# 02_-_Power_Supplies.net
KiCad netlist of a schematic drawn in Altium Designer
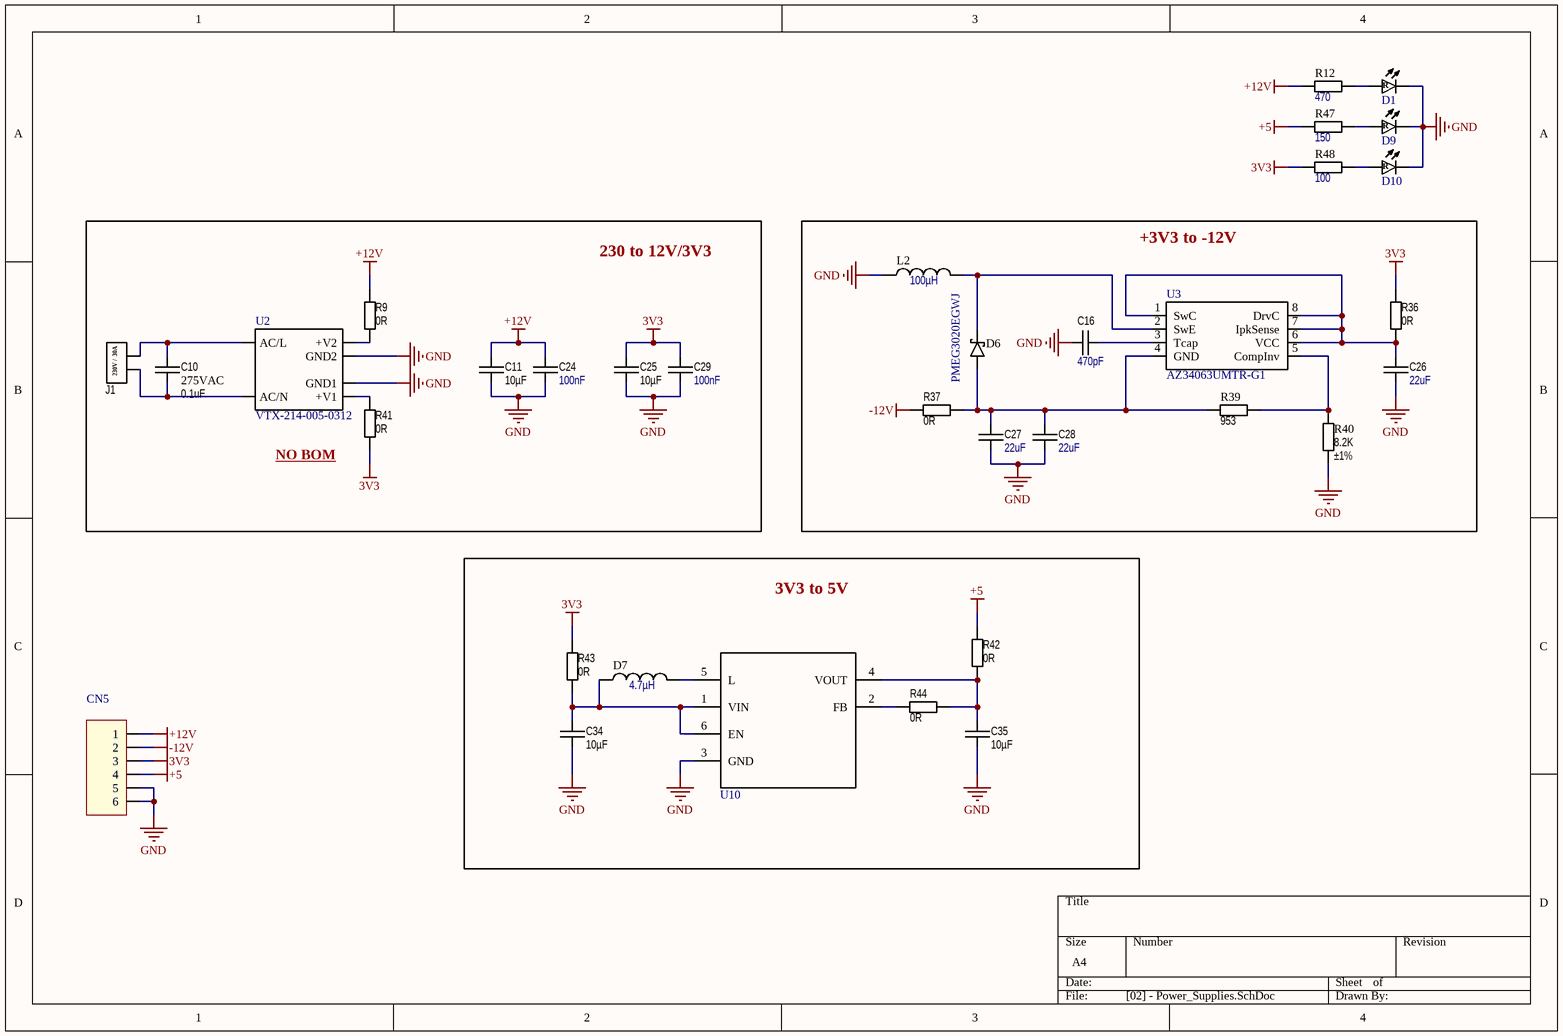
[diagram p0: [02] - Power_Supplies.SchDoc]

(export (version "E")
  (design (tool "Eeschema 10.0.6"))
  (components
    (comp (ref "C10")
      (value "0.1uF")
      (footprint "ECQL")
      (description "0.1µF Film Capacitor 275V  Polyester, Metallized Radial")
      (fields
        (field (name "PARTNUMBER") "ECQ-U2A104ML")
        (field (name "MANUFACTURER") "Panasonic Electronic Components")
        (field (name "VOLTAGE") "275VAC")
      )
      (libsource (lib "myLibrary") (part "CAPC_0.1uF_RADIAL_275VAC"))
    )
    (comp (ref "C11")
      (value "10µF")
      (footprint "CAP 0603/1608")
      (description "10µF ±20% 25V Ceramic Capacitor X5R 0603 (1608 Metric)")
      (fields
        (field (name "PARTNUMBER") "GRM188R61E106MA73D")
        (field (name "MANUFACTURER") "Murata Electronics")
      )
      (libsource (lib "myLibrary") (part "CAPC_10uF_0603_25V"))
    )
    (comp (ref "C16")
      (value "470pF")
      (footprint "CAP 0603/1608")
      (description "470pF ±10% 50V Ceramic Capacitor X7R 0603 (1608 Metric)")
      (fields (field (name "PARTNUMBER") "CC0603KRX7R9BB471") (field (name "MANUFACTURER") "Yageo"))
      (libsource (lib "myLibrary") (part "CAPC_470pF_0603_50V"))
    )
    (comp (ref "C24")
      (value "100nF")
      (footprint "CAP 0603/1608")
      (description "1µF ±10% 16V Ceramic Capacitor X5R 0603 (1608 Metric)")
      (fields (field (name "PARTNUMBER") "CC0603KRX5R7BB105") (field (name "MANUFACTURER") "Yageo"))
      (libsource (lib "myLibrary") (part "CAPC_100NF_0603_50V"))
    )
    (comp (ref "C25")
      (value "10µF")
      (footprint "CAP 0603/1608")
      (description "10µF ±20% 25V Ceramic Capacitor X5R 0603 (1608 Metric)")
      (fields
        (field (name "PARTNUMBER") "GRM188R61E106MA73D")
        (field (name "MANUFACTURER") "Murata Electronics")
      )
      (libsource (lib "myLibrary") (part "CAPC_10uF_0603_25V"))
    )
    (comp (ref "C26")
      (value "22uF")
      (footprint "CAP 0603/1608")
      (description "22µF ±20% 6.3V Ceramic Capacitor X5R 0603 (1608 Metric)")
      (fields
        (field (name "PARTNUMBER") "GRM188R60J226MEA0D")
        (field (name "MANUFACTURER") "Murata Electronics")
      )
      (libsource (lib "myLibrary") (part "CAPC_22uF_0603_6.3V"))
    )
    (comp (ref "C27")
      (value "22uF")
      (footprint "CAP 0603/1608")
      (description "22µF ±20% 6.3V Ceramic Capacitor X5R 0603 (1608 Metric)")
      (fields
        (field (name "PARTNUMBER") "GRM188R60J226MEA0D")
        (field (name "MANUFACTURER") "Murata Electronics")
      )
      (libsource (lib "myLibrary") (part "CAPC_22uF_0603_6.3V"))
    )
    (comp (ref "C28")
      (value "22uF")
      (footprint "CAP 0603/1608")
      (description "22µF ±20% 6.3V Ceramic Capacitor X5R 0603 (1608 Metric)")
      (fields
        (field (name "PARTNUMBER") "GRM188R60J226MEA0D")
        (field (name "MANUFACTURER") "Murata Electronics")
      )
      (libsource (lib "myLibrary") (part "CAPC_22uF_0603_6.3V"))
    )
    (comp (ref "C29")
      (value "100nF")
      (footprint "CAP 0603/1608")
      (description "1µF ±10% 16V Ceramic Capacitor X5R 0603 (1608 Metric)")
      (fields (field (name "PARTNUMBER") "CC0603KRX5R7BB105") (field (name "MANUFACTURER") "Yageo"))
      (libsource (lib "myLibrary") (part "CAPC_100NF_0603_50V"))
    )
    (comp (ref "C34")
      (value "10µF")
      (footprint "CAP 0603/1608")
      (description "10µF ±20% 25V Ceramic Capacitor X5R 0603 (1608 Metric)")
      (fields
        (field (name "PARTNUMBER") "GRM188R61E106MA73D")
        (field (name "MANUFACTURER") "Murata Electronics")
      )
      (libsource (lib "myLibrary") (part "CAPC_10uF_0603_25V"))
    )
    (comp (ref "C35")
      (value "10µF")
      (footprint "CAP 0603/1608")
      (description "10µF ±20% 25V Ceramic Capacitor X5R 0603 (1608 Metric)")
      (fields
        (field (name "PARTNUMBER") "GRM188R61E106MA73D")
        (field (name "MANUFACTURER") "Murata Electronics")
      )
      (libsource (lib "myLibrary") (part "CAPC_10uF_0603_25V"))
    )
    (comp (ref "CN5")
      (value "61300411121")
      (footprint "Terminal_6")
      (description "Connector Header Through Hole 4 position 0.100\" (2.54mm)")
      (fields (field (name "MANUFACTURER") "Wurth Electronics Inc."))
      (libsource (lib "myLibrary") (part "CONN_6POS"))
    )
    (comp (ref "D1")
      (value "SML-D12U1WT86")
      (footprint "LED-0603")
      (description "Red 620nm LED Indication - Discrete 2.2V 0603 (1608 Metric)")
      (fields (field (name "MANUFACTURER") "Rohm Semiconductor"))
      (libsource (lib "myLibrary") (part "LED_RED"))
    )
    (comp (ref "D6")
      (value "PMEG3020EGWJ")
      (footprint "SOD123")
      (description "Diode Schottky 30V 2A Surface Mount SOD-123")
      (fields (field (name "MANUFACTURER") "Nexperia USA Inc."))
      (libsource (lib "myLibrary") (part "DIODE_PMEG"))
    )
    (comp (ref "D7")
      (value "4.7µH")
      (footprint "IND_LQH2HPN4R7MJRL")
      (description "4.7µH Shielded Wirewound Inductor 770mA 204mOhm Max 1008 (2520 Metric)")
      (fields (field (name "PARTNUMBER") "LQH2HPN4R7MJRL") (field (name "MANUFACTURER") "Murata Electronics"))
      (libsource (lib "myLibrary") (part "IND_4.7uH_170mOhm _Murata"))
    )
    (comp (ref "D9")
      (value "SML-D12U1WT86")
      (footprint "LED-0603")
      (description "Red 620nm LED Indication - Discrete 2.2V 0603 (1608 Metric)")
      (fields (field (name "MANUFACTURER") "Rohm Semiconductor"))
      (libsource (lib "myLibrary") (part "LED_RED"))
    )
    (comp (ref "D10")
      (value "SML-D12U1WT86")
      (footprint "LED-0603")
      (description "Red 620nm LED Indication - Discrete 2.2V 0603 (1608 Metric)")
      (fields (field (name "MANUFACTURER") "Rohm Semiconductor"))
      (libsource (lib "myLibrary") (part "LED_RED"))
    )
    (comp (ref "J1")
      (value "1868076")
      (footprint "30Amp_Connector")
      (description "2 Position Wire to Board Terminal Block Horizontal with Board 0.300\" (7.62mm) Through Hole")
      (fields (field (name "MANUFACTURER") "Phoenix Contact"))
      (libsource (lib "myLibrary") (part "TERM_BLK_02_30A"))
    )
    (comp (ref "L2")
      (value "100µH")
      (footprint "IND_1210")
      (description "100µH Unshielded Wirewound Inductor 150mA 1.4Ohm 1210 (3225 Metric)")
      (fields (field (name "PARTNUMBER") "LBC3225T101KR") (field (name "MANUFACTURER") "Taiyo Yuden"))
      (libsource (lib "myLibrary") (part "IND_100uH"))
    )
    (comp (ref "R9")
      (value "0R")
      (footprint "R0603")
      (description "RES 0R 0603 JUMPER")
      (fields (field (name "PARTNUMBER") "RC0603JR-070RL") (field (name "MANUFACTURER") "Yageo"))
      (libsource (lib "myLibrary") (part "RES_0R_0603_JUMPER"))
    )
    (comp (ref "R12")
      (value "470")
      (footprint "R0603")
      (description "470 Ohms ±1% 0.1W, 1/10W Chip Resistor 0603 (1608 Metric) Moisture Resistant Thick Film")
      (fields (field (name "PARTNUMBER") "RC0603FR-07470RL") (field (name "MANUFACTURER") "Yageo"))
      (libsource (lib "myLibrary") (part "RES_470_0603_1%_1"))
    )
    (comp (ref "R36")
      (value "0R")
      (footprint "R0603")
      (description "RES 0R 0603 JUMPER")
      (fields (field (name "PARTNUMBER") "RC0603JR-070RL") (field (name "MANUFACTURER") "Yageo"))
      (libsource (lib "myLibrary") (part "RES_0R_0603_JUMPER"))
    )
    (comp (ref "R37")
      (value "0R")
      (footprint "R0603")
      (description "RES 0R 0603 JUMPER")
      (fields (field (name "PARTNUMBER") "RC0603JR-070RL") (field (name "MANUFACTURER") "Yageo"))
      (libsource (lib "") (part "RES_0R_0603_JUMPER_1"))
    )
    (comp (ref "R39")
      (value "953")
      (footprint "R0603")
      (description "953 Ohms ±1% 0.1W, 1/10W Chip Resistor 0603 (1608 Metric) Moisture Resistant Thick Film")
      (fields (field (name "PARTNUMBER") "RC0603FR-07953RL") (field (name "MANUFACTURER") "Yageo"))
      (libsource (lib "myLibrary") (part "RES_953"))
    )
    (comp (ref "R40")
      (value "8.2K")
      (footprint "R0603")
      (description "8.2 kOhms ±1% 0.125W, 1/8W Chip Resistor 0603 (1608 Metric) Anti-Sulfur Thin Film")
      (fields
        (field (name "PARTNUMBER") "MCT06030C8201FP500")
        (field (name "MANUFACTURER") "Vishay Beyschlag")
        (field (name "TOLERANCE") "±1%")
      )
      (libsource (lib "myLibrary") (part "RES_8K2_0603_1%"))
    )
    (comp (ref "R41")
      (value "0R")
      (footprint "R0603")
      (description "RES 0R 0603 JUMPER")
      (fields (field (name "PARTNUMBER") "RC0603JR-070RL") (field (name "MANUFACTURER") "Yageo"))
      (libsource (lib "myLibrary") (part "RES_0R_0603_JUMPER"))
    )
    (comp (ref "R42")
      (value "0R")
      (footprint "R0603")
      (description "RES 0R 0603 JUMPER")
      (fields (field (name "PARTNUMBER") "RC0603JR-070RL") (field (name "MANUFACTURER") "Yageo"))
      (libsource (lib "") (part "RES_0R_0603_JUMPER_2"))
    )
    (comp (ref "R43")
      (value "0R")
      (footprint "R0603")
      (description "RES 0R 0603 JUMPER")
      (fields (field (name "PARTNUMBER") "RC0603JR-070RL") (field (name "MANUFACTURER") "Yageo"))
      (libsource (lib "") (part "RES_0R_0603_JUMPER_2"))
    )
    (comp (ref "R44")
      (value "0R")
      (footprint "R0603")
      (description "RES 0R 0603 JUMPER")
      (fields (field (name "PARTNUMBER") "RC0603JR-070RL") (field (name "MANUFACTURER") "Yageo"))
      (libsource (lib "") (part "RES_0R_0603_JUMPER_1"))
    )
    (comp (ref "R47")
      (value "150")
      (footprint "R0603")
      (description "150 Ohms ±5% 0.1W, 1/10W Chip Resistor 0603 (1608 Metric) Moisture Resistant Thick Film")
      (fields (field (name "PARTNUMBER") "RC0603JR-07150RL") (field (name "MANUFACTURER") "Yageo"))
      (libsource (lib "myLibrary") (part "RES_150_0603_5%"))
    )
    (comp (ref "R48")
      (value "100")
      (footprint "R0603")
      (description "100 Ohms ±1% 0.1W, 1/10W Chip Resistor 0603 (1608 Metric) Moisture Resistant Thick Film")
      (fields (field (name "PARTNUMBER") "RC0603FR-07100RL") (field (name "MANUFACTURER") "Yageo"))
      (libsource (lib "myLibrary") (part "RES_100_0603_1%"))
    )
    (comp (ref "U2")
      (value "VTX-214-005-0312")
      (footprint "AC-DC_VTX")
      (description "VTX-214-005-0312 -  AC / DC PCB Mount Power Supply (PSU), ITE, 2 Output, 5W, 3.3V, 757mA, 12V")
      (fields (field (name "MANUFACTURER") "VIGORTRONIX"))
      (libsource (lib "myLibrary") (part "AC/DC-VTX"))
    )
    (comp (ref "U3")
      (value "AZ34063UMTR-G1")
      (footprint "SOIC-8")
      (fields (field (name "MANUFACTURER") "Diodes Incorporated"))
      (libsource (lib "myLibrary") (part "IC_REG"))
    )
    (comp (ref "U10")
      (value "TPS61222DCKR")
      (footprint "SC-70-6")
      (description "Boost Switching Regulator IC Positive Fixed 5V 1 Output 200mA (Switch) 6-TSSOP, SC-88, SOT-363")
      (fields (field (name "MANUFACTURER") "Texas Instruments"))
      (libsource (lib "myLibrary") (part "IC_REG_BOOST"))
    )
  )
  (nets
    (net (code "1") (name "+5") (class "Default")
      (node (ref "CN5") (pin "4") (pinfunction "4_4") (pintype "passive"))
      (node (ref "R42") (pin "1") (pinfunction "1_1") (pintype "passive"))
      (node (ref "R47") (pin "1") (pinfunction "1_1") (pintype "passive"))
    )
    (net (code "2") (name "+12V") (class "Default")
      (node (ref "C11") (pin "1") (pintype "passive"))
      (node (ref "C24") (pin "1") (pintype "passive"))
      (node (ref "CN5") (pin "1") (pinfunction "1_1") (pintype "passive"))
      (node (ref "R12") (pin "1") (pinfunction "1_1") (pintype "passive"))
      (node (ref "R9") (pin "2") (pinfunction "2_2") (pintype "passive"))
    )
    (net (code "3") (name "-12V") (class "Default")
      (node (ref "CN5") (pin "2") (pinfunction "2_2") (pintype "passive"))
      (node (ref "R37") (pin "1") (pinfunction "1_1") (pintype "passive"))
    )
    (net (code "4") (name "3V3") (class "Default")
      (node (ref "C25") (pin "1") (pintype "passive"))
      (node (ref "C29") (pin "1") (pintype "passive"))
      (node (ref "CN5") (pin "3") (pinfunction "3_3") (pintype "passive"))
      (node (ref "R36") (pin "2") (pinfunction "2_2") (pintype "passive"))
      (node (ref "R41") (pin "1") (pinfunction "1_1") (pintype "passive"))
      (node (ref "R43") (pin "1") (pinfunction "1_1") (pintype "passive"))
      (node (ref "R48") (pin "1") (pinfunction "1_1") (pintype "passive"))
    )
    (net (code "5") (name "GND") (class "Default")
      (node (ref "C11") (pin "2") (pintype "passive"))
      (node (ref "C16") (pin "1") (pintype "passive"))
      (node (ref "C24") (pin "2") (pintype "passive"))
      (node (ref "C25") (pin "2") (pintype "passive"))
      (node (ref "C26") (pin "1") (pintype "passive"))
      (node (ref "C27") (pin "1") (pintype "passive"))
      (node (ref "C28") (pin "1") (pintype "passive"))
      (node (ref "C29") (pin "2") (pintype "passive"))
      (node (ref "C34") (pin "2") (pintype "passive"))
      (node (ref "C35") (pin "2") (pintype "passive"))
      (node (ref "CN5") (pin "5") (pinfunction "5_5") (pintype "passive"))
      (node (ref "CN5") (pin "6") (pinfunction "6_6") (pintype "passive"))
      (node (ref "D1") (pin "1") (pinfunction "1_1") (pintype "passive"))
      (node (ref "D10") (pin "1") (pinfunction "1_1") (pintype "passive"))
      (node (ref "D9") (pin "1") (pinfunction "1_1") (pintype "passive"))
      (node (ref "L2") (pin "1") (pinfunction "1_1") (pintype "passive"))
      (node (ref "R40") (pin "2") (pinfunction "2_2") (pintype "passive"))
      (node (ref "U10") (pin "3") (pinfunction "GND_3") (pintype "passive"))
      (node (ref "U2") (pin "3") (pinfunction "GND1_3") (pintype "passive"))
      (node (ref "U2") (pin "5") (pinfunction "GND2_5") (pintype "passive"))
    )
    (net (code "6") (name "Net-(D1-Pad2)") (class "Default")
      (node (ref "D1") (pin "2") (pinfunction "2_2") (pintype "passive"))
      (node (ref "R12") (pin "2") (pinfunction "2_2") (pintype "passive"))
    )
    (net (code "7") (name "Net-(D9-Pad2)") (class "Default")
      (node (ref "D9") (pin "2") (pinfunction "2_2") (pintype "passive"))
      (node (ref "R47") (pin "2") (pinfunction "2_2") (pintype "passive"))
    )
    (net (code "8") (name "Net-(D10-Pad2)") (class "Default")
      (node (ref "D10") (pin "2") (pinfunction "2_2") (pintype "passive"))
      (node (ref "R48") (pin "2") (pinfunction "2_2") (pintype "passive"))
    )
    (net (code "9") (name "Net-(U2-+V1)") (class "Default")
      (node (ref "R41") (pin "2") (pinfunction "2_2") (pintype "passive"))
      (node (ref "U2") (pin "4") (pinfunction "+V1_4") (pintype "passive"))
    )
    (net (code "10") (name "Net-(U2-+V2)") (class "Default")
      (node (ref "R9") (pin "1") (pinfunction "1_1") (pintype "passive"))
      (node (ref "U2") (pin "6") (pinfunction "+V2_6") (pintype "passive"))
    )
    (net (code "11") (name "Net-(U2-AC{slash}L)") (class "Default")
      (node (ref "C10") (pin "2") (pintype "passive"))
      (node (ref "J1") (pin "2") (pintype "passive"))
      (node (ref "U2") (pin "1") (pinfunction "AC/L_1") (pintype "passive"))
    )
    (net (code "12") (name "Net-(U2-AC{slash}N)") (class "Default")
      (node (ref "C10") (pin "1") (pintype "passive"))
      (node (ref "J1") (pin "1") (pintype "passive"))
      (node (ref "U2") (pin "2") (pinfunction "AC/N_2") (pintype "passive"))
    )
    (net (code "13") (name "Net-(U3-CompInv)") (class "Default")
      (node (ref "R39") (pin "2") (pinfunction "2_2") (pintype "passive"))
      (node (ref "R40") (pin "1") (pinfunction "1_1") (pintype "passive"))
      (node (ref "U3") (pin "5") (pinfunction "CompInv_5") (pintype "passive"))
    )
    (net (code "14") (name "Net-(U3-DrvC)") (class "Default")
      (node (ref "C26") (pin "2") (pintype "passive"))
      (node (ref "R36") (pin "1") (pinfunction "1_1") (pintype "passive"))
      (node (ref "U3") (pin "1") (pinfunction "SwC_1") (pintype "passive"))
      (node (ref "U3") (pin "6") (pinfunction "VCC_6") (pintype "passive"))
      (node (ref "U3") (pin "7") (pinfunction "IpkSense_7") (pintype "passive"))
      (node (ref "U3") (pin "8") (pinfunction "DrvC_8") (pintype "passive"))
    )
    (net (code "15") (name "Net-(U3-GND)") (class "Default")
      (node (ref "C27") (pin "2") (pintype "passive"))
      (node (ref "C28") (pin "2") (pintype "passive"))
      (node (ref "D6") (pin "A") (pinfunction "A_A") (pintype "passive"))
      (node (ref "R37") (pin "2") (pinfunction "2_2") (pintype "passive"))
      (node (ref "R39") (pin "1") (pinfunction "1_1") (pintype "passive"))
      (node (ref "U3") (pin "4") (pinfunction "GND_4") (pintype "passive"))
    )
    (net (code "16") (name "Net-(U3-SwE)") (class "Default")
      (node (ref "D6") (pin "C") (pinfunction "C_C") (pintype "passive"))
      (node (ref "L2") (pin "2") (pinfunction "2_2") (pintype "passive"))
      (node (ref "U3") (pin "2") (pinfunction "SwE_2") (pintype "passive"))
    )
    (net (code "17") (name "Net-(U3-Tcap)") (class "Default")
      (node (ref "C16") (pin "2") (pintype "passive"))
      (node (ref "U3") (pin "3") (pinfunction "Tcap_3") (pintype "passive"))
    )
    (net (code "18") (name "Net-(U10-EN)") (class "Default")
      (node (ref "C34") (pin "1") (pintype "passive"))
      (node (ref "D7") (pin "1") (pinfunction "1_1") (pintype "passive"))
      (node (ref "R43") (pin "2") (pinfunction "2_2") (pintype "passive"))
      (node (ref "U10") (pin "1") (pinfunction "VIN_1") (pintype "passive"))
      (node (ref "U10") (pin "6") (pinfunction "EN_6") (pintype "passive"))
    )
    (net (code "19") (name "Net-(U10-FB)") (class "Default")
      (node (ref "R44") (pin "1") (pinfunction "1_1") (pintype "passive"))
      (node (ref "U10") (pin "2") (pinfunction "FB_2") (pintype "passive"))
    )
    (net (code "20") (name "Net-(U10-L)") (class "Default")
      (node (ref "D7") (pin "2") (pinfunction "2_2") (pintype "passive"))
      (node (ref "U10") (pin "5") (pinfunction "L_5") (pintype "passive"))
    )
    (net (code "21") (name "Net-(U10-VOUT)") (class "Default")
      (node (ref "C35") (pin "1") (pintype "passive"))
      (node (ref "R42") (pin "2") (pinfunction "2_2") (pintype "passive"))
      (node (ref "R44") (pin "2") (pinfunction "2_2") (pintype "passive"))
      (node (ref "U10") (pin "4") (pinfunction "VOUT_4") (pintype "passive"))
    )
  )
)
